# scsi2sd.net
KiCad netlist of a schematic drawn in EAGLE
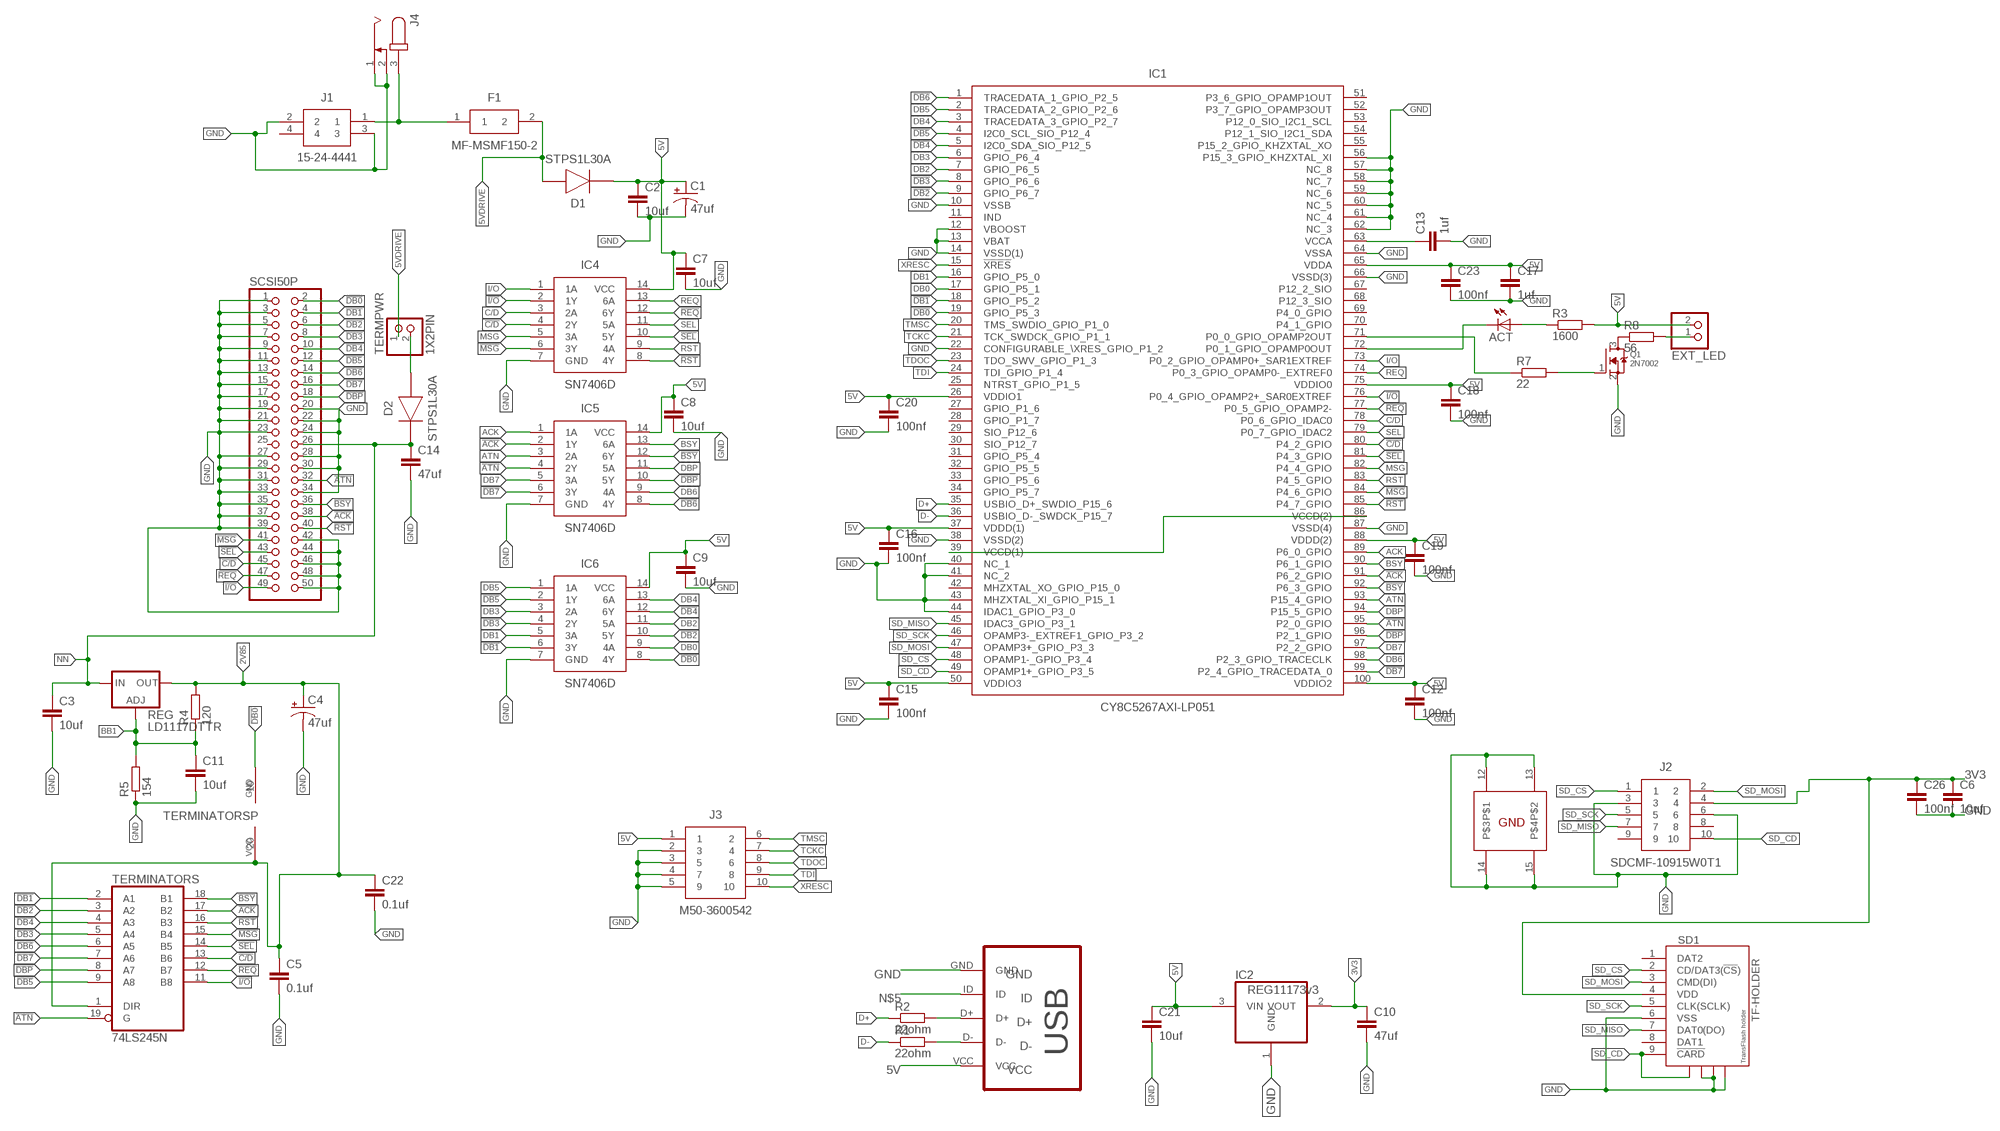
[diagram p0: schematic, sheet 1]

(export (version "E")
  (design (tool "Eeschema 10.0.6"))
  (components
    (comp (ref "ACT")
      (value "LEDCHIPLED_0805")
      (footprint "eagle-import:CHIPLED_0805")
      (libsource (lib "eagle-import") (part "LEDCHIPLED_0805"))
    )
    (comp (ref "C1")
      (value "47uf")
      (footprint "eagle-import:E2,5-5")
      (libsource (lib "eagle-import") (part "CPOL-USE2.5-5"))
    )
    (comp (ref "C2")
      (value "10uf")
      (footprint "eagle-import:C0603")
      (libsource (lib "eagle-import") (part "C-EUC0603"))
    )
    (comp (ref "C3")
      (value "10uf")
      (footprint "eagle-import:C0603")
      (libsource (lib "eagle-import") (part "C-EUC0603"))
    )
    (comp (ref "C4")
      (value "47uf")
      (footprint "eagle-import:E2,5-5")
      (libsource (lib "eagle-import") (part "CPOL-USE2.5-5"))
    )
    (comp (ref "C5")
      (value "0.1uf")
      (footprint "eagle-import:C0603")
      (libsource (lib "eagle-import") (part "C-EUC0603"))
    )
    (comp (ref "C6")
      (value "10uf")
      (footprint "eagle-import:C0603")
      (libsource (lib "eagle-import") (part "C-EUC0603"))
    )
    (comp (ref "C7")
      (value "10uf")
      (footprint "eagle-import:C0603")
      (libsource (lib "eagle-import") (part "C-EUC0603"))
    )
    (comp (ref "C8")
      (value "10uf")
      (footprint "eagle-import:C0603")
      (libsource (lib "eagle-import") (part "C-EUC0603"))
    )
    (comp (ref "C9")
      (value "10uf")
      (footprint "eagle-import:C0603")
      (libsource (lib "eagle-import") (part "C-EUC0603"))
    )
    (comp (ref "C10")
      (value "47uf")
      (footprint "eagle-import:C0603")
      (libsource (lib "eagle-import") (part "C-EUC0603"))
    )
    (comp (ref "C11")
      (value "10uf")
      (footprint "eagle-import:C0603")
      (libsource (lib "eagle-import") (part "C-EUC0603"))
    )
    (comp (ref "C12")
      (value "100nf")
      (footprint "eagle-import:C0603")
      (libsource (lib "eagle-import") (part "C-EUC0603"))
    )
    (comp (ref "C13")
      (value "1uf")
      (footprint "eagle-import:C0603")
      (libsource (lib "eagle-import") (part "C-EUC0603"))
    )
    (comp (ref "C14")
      (value "47uf")
      (footprint "eagle-import:C1206")
      (libsource (lib "eagle-import") (part "C-EUC1206"))
    )
    (comp (ref "C15")
      (value "100nf")
      (footprint "eagle-import:C0603")
      (libsource (lib "eagle-import") (part "C-EUC0603"))
    )
    (comp (ref "C16")
      (value "100nf")
      (footprint "eagle-import:C0603")
      (libsource (lib "eagle-import") (part "C-EUC0603"))
    )
    (comp (ref "C17")
      (value "1uf")
      (footprint "eagle-import:C0603")
      (libsource (lib "eagle-import") (part "C-EUC0603"))
    )
    (comp (ref "C18")
      (value "100nf")
      (footprint "eagle-import:C0603")
      (libsource (lib "eagle-import") (part "C-EUC0603"))
    )
    (comp (ref "C19")
      (value "100nf")
      (footprint "eagle-import:C0603")
      (libsource (lib "eagle-import") (part "C-EUC0603"))
    )
    (comp (ref "C20")
      (value "100nf")
      (footprint "eagle-import:C0603")
      (libsource (lib "eagle-import") (part "C-EUC0603"))
    )
    (comp (ref "C21")
      (value "10uf")
      (footprint "eagle-import:C0603")
      (libsource (lib "eagle-import") (part "C-EUC0603"))
    )
    (comp (ref "C22")
      (value "0.1uf")
      (footprint "eagle-import:C0603")
      (libsource (lib "eagle-import") (part "C-EUC0603"))
    )
    (comp (ref "C23")
      (value "100nf")
      (footprint "eagle-import:C0603")
      (libsource (lib "eagle-import") (part "C-EUC0603"))
    )
    (comp (ref "C26")
      (value "100nf")
      (footprint "eagle-import:C0603")
      (libsource (lib "eagle-import") (part "C-EUC0603"))
    )
    (comp (ref "D1")
      (value "STPS1L30A")
      (footprint "eagle-import:DIOM5226X223N")
      (fields (field (name "RS_PART_NUMBER") "4858061"))
      (libsource (lib "eagle-import") (part "STPS1L30A"))
    )
    (comp (ref "D2")
      (value "STPS1L30A")
      (footprint "eagle-import:DIOM5226X223N")
      (fields (field (name "RS_PART_NUMBER") "4858061"))
      (libsource (lib "eagle-import") (part "STPS1L30A"))
    )
    (comp (ref "EXT_LED")
      (value "1X2PIN")
      (footprint "eagle-import:1X2PIN")
      (libsource (lib "eagle-import") (part "1X2PIN"))
    )
    (comp (ref "F1")
      (value "MF-MSMF150-2")
      (footprint "eagle-import:FUSC4632X85N")
      (fields (field (name "RS_PART_NUMBER") "6478235"))
      (libsource (lib "eagle-import") (part "MF-MSMF150-2"))
    )
    (comp (ref "IC1")
      (value "CY8C5267AXI-LP051")
      (footprint "eagle-import:TQFP50P1600X1600X160-100N")
      (fields (field (name "RS_PART_NUMBER") "8282749"))
      (libsource (lib "eagle-import") (part "CY8C5267AXI-LP051"))
    )
    (comp (ref "IC2")
      (value "REG11173v3")
      (footprint "eagle-import:SOT223")
      (fields (field (name "MPN") "REG1117"))
      (libsource (lib "eagle-import") (part "REG1117"))
    )
    (comp (ref "IC4")
      (value "SN7406D")
      (footprint "eagle-import:SOIC127P600X175-14N")
      (fields (field (name "RS_PART_NUMBER") "6630739"))
      (libsource (lib "eagle-import") (part "SN7406D"))
    )
    (comp (ref "IC5")
      (value "SN7406D")
      (footprint "eagle-import:SOIC127P600X175-14N")
      (fields (field (name "RS_PART_NUMBER") "6630739"))
      (libsource (lib "eagle-import") (part "SN7406D"))
    )
    (comp (ref "IC6")
      (value "SN7406D")
      (footprint "eagle-import:SOIC127P600X175-14N")
      (fields (field (name "RS_PART_NUMBER") "6630739"))
      (libsource (lib "eagle-import") (part "SN7406D"))
    )
    (comp (ref "J1")
      (value "15-24-4441")
      (footprint "eagle-import:15-24-4441")
      (fields (field (name "RS_PART_NUMBER") "6704256"))
      (libsource (lib "eagle-import") (part "15-24-4441"))
    )
    (comp (ref "J2")
      (value "SDCMF-10915W0T1")
      (footprint "eagle-import:SDCMF-10915W0T1")
      (libsource (lib "eagle-import") (part "SDCMF-10915W0T1"))
    )
    (comp (ref "J3")
      (value "M50-3600542")
      (footprint "eagle-import:HARWIN_10PIN_1.27PITCH_SMD")
      (fields (field (name "RS_PART_NUMBER") "1224772"))
      (libsource (lib "eagle-import") (part "M50-3600542"))
    )
    (comp (ref "J4")
      (value "RAPC7120")
      (footprint "eagle-import:RAPC712")
      (libsource (lib "eagle-import") (part "RAPC7120"))
    )
    (comp (ref "Q1")
      (value "2N7002")
      (footprint "eagle-import:SOT23")
      (libsource (lib "eagle-import") (part "MOSFET-NREFLOW"))
    )
    (comp (ref "R1")
      (value "22ohm")
      (footprint "eagle-import:R0603")
      (libsource (lib "eagle-import") (part "R-EU_R0603"))
    )
    (comp (ref "R2")
      (value "22ohm")
      (footprint "eagle-import:R0603")
      (libsource (lib "eagle-import") (part "R-EU_R0603"))
    )
    (comp (ref "R3")
      (value "1600")
      (footprint "eagle-import:R0603")
      (libsource (lib "eagle-import") (part "R-EU_R0603"))
    )
    (comp (ref "R4")
      (value "120")
      (footprint "eagle-import:R0603")
      (libsource (lib "eagle-import") (part "R-EU_R0603"))
    )
    (comp (ref "R5")
      (value "154")
      (footprint "eagle-import:R0603")
      (libsource (lib "eagle-import") (part "R-EU_R0603"))
    )
    (comp (ref "R7")
      (value "22")
      (footprint "eagle-import:R0603")
      (libsource (lib "eagle-import") (part "R-EU_R0603"))
    )
    (comp (ref "R8")
      (value "56")
      (footprint "eagle-import:R0603")
      (libsource (lib "eagle-import") (part "R-EU_R0603"))
    )
    (comp (ref "REG")
      (value "LD1117DTTR")
      (footprint "eagle-import:DPACK")
      (libsource (lib "eagle-import") (part "LD117A?DT12TR"))
    )
    (comp (ref "SCSI50P")
      (value "PINHD-2X25/90")
      (footprint "eagle-import:2X25_90")
      (libsource (lib "eagle-import") (part "PINHD-2X25/90"))
    )
    (comp (ref "SD1")
      (value "TF-HOLDER")
      (footprint "eagle-import:TF-PULL")
      (libsource (lib "eagle-import") (part "TF-HOLDER"))
    )
    (comp (ref "TERMINATORS")
      (value "74LS245N")
      (footprint "eagle-import:DIL20")
      (libsource (lib "eagle-import") (part "74245NLS"))
    )
    (comp (ref "TERMPWR")
      (value "1X2PIN")
      (footprint "eagle-import:1X2PIN")
      (libsource (lib "eagle-import") (part "edu_1X2PIN"))
    )
    (comp (ref "USB")
      (value "MICRO-USB-B")
      (footprint "eagle-import:MICRO_USB_4_LEGS")
      (libsource (lib "eagle-import") (part "MICRO-USB-B"))
    )
  )
  (nets
    (net (code "1") (name "/N$5") (class "Default")
      (node (ref "USB") (pin "ID") (pinfunction "ID_ID") (pintype "bidirectional"))
    )
    (net (code "2") (name "/~{ACK}") (class "Default")
      (node (ref "IC1") (pin "91") (pinfunction "P6_2_GPIO_91") (pintype "input"))
      (node (ref "IC5") (pin "2") (pinfunction "1Y_2") (pintype "input"))
      (node (ref "SCSI50P") (pin "38") (pinfunction "38_38") (pintype "passive"))
      (node (ref "TERMINATORS") (pin "17") (pinfunction "B2_17") (pintype "bidirectional"))
    )
    (net (code "3") (name "/~{ATN}") (class "Default")
      (node (ref "IC1") (pin "95") (pinfunction "P2_0_GPIO_95") (pintype "input"))
      (node (ref "IC5") (pin "4") (pinfunction "2Y_4") (pintype "input"))
      (node (ref "SCSI50P") (pin "32") (pinfunction "32_32") (pintype "passive"))
      (node (ref "TERMINATORS") (pin "19") (pinfunction "G_19") (pintype "input"))
    )
    (net (code "4") (name "/~{BSY}") (class "Default")
      (node (ref "IC1") (pin "92") (pinfunction "P6_3_GPIO_92") (pintype "input"))
      (node (ref "IC5") (pin "12") (pinfunction "6Y_12") (pintype "input"))
      (node (ref "SCSI50P") (pin "36") (pinfunction "36_36") (pintype "passive"))
      (node (ref "TERMINATORS") (pin "18") (pinfunction "B1_18") (pintype "bidirectional"))
    )
    (net (code "5") (name "/~{C{slash}D}") (class "Default")
      (node (ref "IC1") (pin "80") (pinfunction "P4_2_GPIO_80") (pintype "input"))
      (node (ref "IC4") (pin "4") (pinfunction "2Y_4") (pintype "input"))
      (node (ref "SCSI50P") (pin "45") (pinfunction "45_45") (pintype "passive"))
      (node (ref "TERMINATORS") (pin "13") (pinfunction "B6_13") (pintype "bidirectional"))
    )
    (net (code "6") (name "/~{DB0}") (class "Default")
      (node (ref "IC1") (pin "19") (pinfunction "GPIO_P5_3_19") (pintype "input"))
      (node (ref "IC6") (pin "8") (pinfunction "4Y_8") (pintype "input"))
      (node (ref "SCSI50P") (pin "2") (pinfunction "2_2") (pintype "passive"))
      (node (ref "TERMINATORS") (pin "10") (pinfunction "GND_10") (pintype "power_in"))
    )
    (net (code "7") (name "/~{DB1}") (class "Default")
      (node (ref "IC1") (pin "18") (pinfunction "GPIO_P5_2_18") (pintype "input"))
      (node (ref "IC6") (pin "6") (pinfunction "3Y_6") (pintype "input"))
      (node (ref "SCSI50P") (pin "4") (pinfunction "4_4") (pintype "passive"))
      (node (ref "TERMINATORS") (pin "2") (pinfunction "A1_2") (pintype "bidirectional"))
    )
    (net (code "8") (name "/~{DB2}") (class "Default")
      (node (ref "IC1") (pin "9") (pinfunction "GPIO_P6_7_9") (pintype "input"))
      (node (ref "IC6") (pin "10") (pinfunction "5Y_10") (pintype "input"))
      (node (ref "SCSI50P") (pin "6") (pinfunction "6_6") (pintype "passive"))
      (node (ref "TERMINATORS") (pin "3") (pinfunction "A2_3") (pintype "bidirectional"))
    )
    (net (code "9") (name "/~{DB3}") (class "Default")
      (node (ref "IC1") (pin "8") (pinfunction "GPIO_P6_6_8") (pintype "input"))
      (node (ref "IC6") (pin "4") (pinfunction "2Y_4") (pintype "input"))
      (node (ref "SCSI50P") (pin "8") (pinfunction "8_8") (pintype "passive"))
      (node (ref "TERMINATORS") (pin "5") (pinfunction "A4_5") (pintype "bidirectional"))
    )
    (net (code "10") (name "/~{DB4}") (class "Default")
      (node (ref "IC1") (pin "5") (pinfunction "I2C0_SDA_SIO_P12_5_5") (pintype "input"))
      (node (ref "IC6") (pin "12") (pinfunction "6Y_12") (pintype "input"))
      (node (ref "SCSI50P") (pin "10") (pinfunction "10_10") (pintype "passive"))
      (node (ref "TERMINATORS") (pin "4") (pinfunction "A3_4") (pintype "bidirectional"))
    )
    (net (code "11") (name "/~{DB5}") (class "Default")
      (node (ref "IC1") (pin "4") (pinfunction "I2C0_SCL_SIO_P12_4_4") (pintype "input"))
      (node (ref "IC6") (pin "2") (pinfunction "1Y_2") (pintype "input"))
      (node (ref "SCSI50P") (pin "12") (pinfunction "12_12") (pintype "passive"))
      (node (ref "TERMINATORS") (pin "9") (pinfunction "A8_9") (pintype "bidirectional"))
    )
    (net (code "12") (name "/~{DB6}") (class "Default")
      (node (ref "IC1") (pin "1") (pinfunction "TRACEDATA_1_GPIO_P2_5_1") (pintype "input"))
      (node (ref "IC5") (pin "8") (pinfunction "4Y_8") (pintype "input"))
      (node (ref "SCSI50P") (pin "14") (pinfunction "14_14") (pintype "passive"))
      (node (ref "TERMINATORS") (pin "6") (pinfunction "A5_6") (pintype "bidirectional"))
    )
    (net (code "13") (name "/~{DB7}") (class "Default")
      (node (ref "IC1") (pin "99") (pinfunction "P2_4_GPIO_TRACEDATA_0_99") (pintype "input"))
      (node (ref "IC5") (pin "6") (pinfunction "3Y_6") (pintype "input"))
      (node (ref "SCSI50P") (pin "16") (pinfunction "16_16") (pintype "passive"))
      (node (ref "TERMINATORS") (pin "7") (pinfunction "A6_7") (pintype "bidirectional"))
    )
    (net (code "14") (name "/~{DBP}") (class "Default")
      (node (ref "IC1") (pin "96") (pinfunction "P2_1_GPIO_96") (pintype "input"))
      (node (ref "IC5") (pin "10") (pinfunction "5Y_10") (pintype "input"))
      (node (ref "SCSI50P") (pin "18") (pinfunction "18_18") (pintype "passive"))
      (node (ref "TERMINATORS") (pin "8") (pinfunction "A7_8") (pintype "bidirectional"))
    )
    (net (code "15") (name "/~{I{slash}O}") (class "Default")
      (node (ref "IC1") (pin "76") (pinfunction "P0_4_GPIO_OPAMP2+_SAR0EXTREF_76") (pintype "input"))
      (node (ref "IC4") (pin "2") (pinfunction "1Y_2") (pintype "input"))
      (node (ref "SCSI50P") (pin "49") (pinfunction "49_49") (pintype "passive"))
      (node (ref "TERMINATORS") (pin "11") (pinfunction "B8_11") (pintype "bidirectional"))
    )
    (net (code "16") (name "/~{MSG}") (class "Default")
      (node (ref "IC1") (pin "84") (pinfunction "P4_6_GPIO_84") (pintype "input"))
      (node (ref "IC4") (pin "6") (pinfunction "3Y_6") (pintype "input"))
      (node (ref "SCSI50P") (pin "41") (pinfunction "41_41") (pintype "passive"))
      (node (ref "TERMINATORS") (pin "15") (pinfunction "B4_15") (pintype "bidirectional"))
    )
    (net (code "17") (name "/~{REQ}") (class "Default")
      (node (ref "IC1") (pin "77") (pinfunction "P0_5_GPIO_OPAMP2-_77") (pintype "input"))
      (node (ref "IC4") (pin "12") (pinfunction "6Y_12") (pintype "input"))
      (node (ref "SCSI50P") (pin "47") (pinfunction "47_47") (pintype "passive"))
      (node (ref "TERMINATORS") (pin "12") (pinfunction "B7_12") (pintype "bidirectional"))
    )
    (net (code "18") (name "/~{RST}") (class "Default")
      (node (ref "IC1") (pin "85") (pinfunction "P4_7_GPIO_85") (pintype "input"))
      (node (ref "IC4") (pin "8") (pinfunction "4Y_8") (pintype "input"))
      (node (ref "SCSI50P") (pin "40") (pinfunction "40_40") (pintype "passive"))
      (node (ref "TERMINATORS") (pin "16") (pinfunction "B3_16") (pintype "bidirectional"))
    )
    (net (code "19") (name "/~{SEL}") (class "Default")
      (node (ref "IC1") (pin "81") (pinfunction "P4_3_GPIO_81") (pintype "input"))
      (node (ref "IC4") (pin "10") (pinfunction "5Y_10") (pintype "input"))
      (node (ref "SCSI50P") (pin "43") (pinfunction "43_43") (pintype "passive"))
      (node (ref "TERMINATORS") (pin "14") (pinfunction "B5_14") (pintype "bidirectional"))
    )
    (net (code "20") (name "2V85") (class "Default")
      (node (ref "C22") (pin "1") (pinfunction "1_1") (pintype "passive"))
      (node (ref "C4") (pin "+") (pinfunction "+_+") (pintype "passive"))
      (node (ref "C5") (pin "1") (pinfunction "1_1") (pintype "passive"))
      (node (ref "R4") (pin "2") (pinfunction "2_2") (pintype "passive"))
      (node (ref "REG") (pin "4") (pinfunction "OUT_4") (pintype "passive"))
      (node (ref "TERMINATORS") (pin "1") (pinfunction "DIR_1") (pintype "input"))
      (node (ref "TERMINATORS") (pin "20") (pinfunction "VCC_20") (pintype "power_in"))
    )
    (net (code "21") (name "3V3") (class "Default")
      (node (ref "C10") (pin "1") (pinfunction "1_1") (pintype "passive"))
      (node (ref "C26") (pin "1") (pinfunction "1_1") (pintype "passive"))
      (node (ref "C6") (pin "1") (pinfunction "1_1") (pintype "passive"))
      (node (ref "IC2") (pin "2") (pinfunction "VOUT_2") (pintype "output"))
      (node (ref "J2") (pin "4") (pinfunction "4_4") (pintype "input"))
      (node (ref "SD1") (pin "4") (pinfunction "VDD_4") (pintype "power_in"))
    )
    (net (code "22") (name "5V") (class "Default")
      (node (ref "C1") (pin "+") (pinfunction "+_+") (pintype "passive"))
      (node (ref "C12") (pin "1") (pinfunction "1_1") (pintype "passive"))
      (node (ref "C15") (pin "1") (pinfunction "1_1") (pintype "passive"))
      (node (ref "C16") (pin "1") (pinfunction "1_1") (pintype "passive"))
      (node (ref "C17") (pin "1") (pinfunction "1_1") (pintype "passive"))
      (node (ref "C18") (pin "1") (pinfunction "1_1") (pintype "passive"))
      (node (ref "C19") (pin "1") (pinfunction "1_1") (pintype "passive"))
      (node (ref "C2") (pin "1") (pinfunction "1_1") (pintype "passive"))
      (node (ref "C20") (pin "1") (pinfunction "1_1") (pintype "passive"))
      (node (ref "C21") (pin "1") (pinfunction "1_1") (pintype "passive"))
      (node (ref "C23") (pin "1") (pinfunction "1_1") (pintype "passive"))
      (node (ref "C7") (pin "1") (pinfunction "1_1") (pintype "passive"))
      (node (ref "C8") (pin "1") (pinfunction "1_1") (pintype "passive"))
      (node (ref "C9") (pin "1") (pinfunction "1_1") (pintype "passive"))
      (node (ref "D1") (pin "1") (pinfunction "K_1") (pintype "bidirectional"))
      (node (ref "EXT_LED") (pin "2") (pinfunction "2_2") (pintype "passive"))
      (node (ref "IC1") (pin "100") (pinfunction "VDDIO2_100") (pintype "input"))
      (node (ref "IC1") (pin "26") (pinfunction "VDDIO1_26") (pintype "input"))
      (node (ref "IC1") (pin "37") (pinfunction "VDDD(1)_37") (pintype "input"))
      (node (ref "IC1") (pin "50") (pinfunction "VDDIO3_50") (pintype "input"))
      (node (ref "IC1") (pin "65") (pinfunction "VDDA_65") (pintype "input"))
      (node (ref "IC1") (pin "75") (pinfunction "VDDIO0_75") (pintype "input"))
      (node (ref "IC1") (pin "88") (pinfunction "VDDD(2)_88") (pintype "input"))
      (node (ref "IC2") (pin "3") (pinfunction "VIN_3") (pintype "input"))
      (node (ref "IC4") (pin "14") (pinfunction "VCC_14") (pintype "input"))
      (node (ref "IC5") (pin "14") (pinfunction "VCC_14") (pintype "input"))
      (node (ref "IC6") (pin "14") (pinfunction "VCC_14") (pintype "input"))
      (node (ref "J3") (pin "1") (pinfunction "1_1") (pintype "input"))
      (node (ref "R3") (pin "2") (pinfunction "2_2") (pintype "passive"))
      (node (ref "USB") (pin "VCC") (pinfunction "VCC_VCC") (pintype "bidirectional"))
    )
    (net (code "23") (name "5VDRIVE") (class "Default")
      (node (ref "D1") (pin "2") (pinfunction "A_2") (pintype "bidirectional"))
      (node (ref "F1") (pin "2") (pinfunction "2_2") (pintype "input"))
      (node (ref "TERMPWR") (pin "1") (pinfunction "1_1") (pintype "passive"))
    )
    (net (code "24") (name "ACK") (class "Default")
      (node (ref "IC1") (pin "89") (pinfunction "P6_0_GPIO_89") (pintype "input"))
      (node (ref "IC5") (pin "1") (pinfunction "1A_1") (pintype "input"))
    )
    (net (code "25") (name "ATN") (class "Default")
      (node (ref "IC1") (pin "93") (pinfunction "P15_4_GPIO_93") (pintype "input"))
      (node (ref "IC5") (pin "3") (pinfunction "2A_3") (pintype "input"))
    )
    (net (code "26") (name "BB1") (class "Default")
      (node (ref "C11") (pin "1") (pinfunction "1_1") (pintype "passive"))
      (node (ref "R4") (pin "1") (pinfunction "1_1") (pintype "passive"))
      (node (ref "R5") (pin "2") (pinfunction "2_2") (pintype "passive"))
      (node (ref "REG") (pin "1") (pinfunction "ADJ_1") (pintype "input"))
    )
    (net (code "27") (name "BSY") (class "Default")
      (node (ref "IC1") (pin "90") (pinfunction "P6_1_GPIO_90") (pintype "input"))
      (node (ref "IC5") (pin "13") (pinfunction "6A_13") (pintype "input"))
    )
    (net (code "28") (name "C{slash}D") (class "Default")
      (node (ref "IC1") (pin "78") (pinfunction "P0_6_GPIO_IDAC0_78") (pintype "input"))
      (node (ref "IC4") (pin "3") (pinfunction "2A_3") (pintype "input"))
    )
    (net (code "29") (name "D+") (class "Default")
      (node (ref "IC1") (pin "35") (pinfunction "USBIO_D+_SWDIO_P15_6_35") (pintype "input"))
      (node (ref "R2") (pin "1") (pinfunction "1_1") (pintype "passive"))
    )
    (net (code "30") (name "D-") (class "Default")
      (node (ref "IC1") (pin "36") (pinfunction "USBIO_D-_SWDCK_P15_7_36") (pintype "input"))
      (node (ref "R1") (pin "1") (pinfunction "1_1") (pintype "passive"))
    )
    (net (code "31") (name "DB0") (class "Default")
      (node (ref "IC1") (pin "17") (pinfunction "GPIO_P5_1_17") (pintype "input"))
      (node (ref "IC6") (pin "9") (pinfunction "4A_9") (pintype "input"))
    )
    (net (code "32") (name "DB1") (class "Default")
      (node (ref "IC1") (pin "16") (pinfunction "GPIO_P5_0_16") (pintype "input"))
      (node (ref "IC6") (pin "5") (pinfunction "3A_5") (pintype "input"))
    )
    (net (code "33") (name "DB2") (class "Default")
      (node (ref "IC1") (pin "7") (pinfunction "GPIO_P6_5_7") (pintype "input"))
      (node (ref "IC6") (pin "11") (pinfunction "5A_11") (pintype "input"))
    )
    (net (code "34") (name "DB3") (class "Default")
      (node (ref "IC1") (pin "6") (pinfunction "GPIO_P6_4_6") (pintype "input"))
      (node (ref "IC6") (pin "3") (pinfunction "2A_3") (pintype "input"))
    )
    (net (code "35") (name "DB4") (class "Default")
      (node (ref "IC1") (pin "3") (pinfunction "TRACEDATA_3_GPIO_P2_7_3") (pintype "input"))
      (node (ref "IC6") (pin "13") (pinfunction "6A_13") (pintype "input"))
    )
    (net (code "36") (name "DB5") (class "Default")
      (node (ref "IC1") (pin "2") (pinfunction "TRACEDATA_2_GPIO_P2_6_2") (pintype "input"))
      (node (ref "IC6") (pin "1") (pinfunction "1A_1") (pintype "input"))
    )
    (net (code "37") (name "DB6") (class "Default")
      (node (ref "IC1") (pin "98") (pinfunction "P2_3_GPIO_TRACECLK_98") (pintype "input"))
      (node (ref "IC5") (pin "9") (pinfunction "4A_9") (pintype "input"))
    )
    (net (code "38") (name "DB7") (class "Default")
      (node (ref "IC1") (pin "97") (pinfunction "P2_2_GPIO_97") (pintype "input"))
      (node (ref "IC5") (pin "5") (pinfunction "3A_5") (pintype "input"))
    )
    (net (code "39") (name "DBP") (class "Default")
      (node (ref "IC1") (pin "94") (pinfunction "P15_5_GPIO_94") (pintype "input"))
      (node (ref "IC5") (pin "11") (pinfunction "5A_11") (pintype "input"))
    )
    (net (code "40") (name "GND") (class "Default")
      (node (ref "C1") (pin "-") (pinfunction "-_-") (pintype "passive"))
      (node (ref "C10") (pin "2") (pinfunction "2_2") (pintype "passive"))
      (node (ref "C11") (pin "2") (pinfunction "2_2") (pintype "passive"))
      (node (ref "C12") (pin "2") (pinfunction "2_2") (pintype "passive"))
      (node (ref "C13") (pin "2") (pinfunction "2_2") (pintype "passive"))
      (node (ref "C14") (pin "2") (pinfunction "2_2") (pintype "passive"))
      (node (ref "C15") (pin "2") (pinfunction "2_2") (pintype "passive"))
      (node (ref "C16") (pin "2") (pinfunction "2_2") (pintype "passive"))
      (node (ref "C17") (pin "2") (pinfunction "2_2") (pintype "passive"))
      (node (ref "C18") (pin "2") (pinfunction "2_2") (pintype "passive"))
      (node (ref "C19") (pin "2") (pinfunction "2_2") (pintype "passive"))
      (node (ref "C2") (pin "2") (pinfunction "2_2") (pintype "passive"))
      (node (ref "C20") (pin "2") (pinfunction "2_2") (pintype "passive"))
      (node (ref "C21") (pin "2") (pinfunction "2_2") (pintype "passive"))
      (node (ref "C22") (pin "2") (pinfunction "2_2") (pintype "passive"))
      (node (ref "C23") (pin "2") (pinfunction "2_2") (pintype "passive"))
      (node (ref "C26") (pin "2") (pinfunction "2_2") (pintype "passive"))
      (node (ref "C3") (pin "2") (pinfunction "2_2") (pintype "passive"))
      (node (ref "C4") (pin "-") (pinfunction "-_-") (pintype "passive"))
      (node (ref "C5") (pin "2") (pinfunction "2_2") (pintype "passive"))
      (node (ref "C6") (pin "2") (pinfunction "2_2") (pintype "passive"))
      (node (ref "C7") (pin "2") (pinfunction "2_2") (pintype "passive"))
      (node (ref "C8") (pin "2") (pinfunction "2_2") (pintype "passive"))
      (node (ref "C9") (pin "2") (pinfunction "2_2") (pintype "passive"))
      (node (ref "IC1") (pin "10") (pinfunction "VSSB_10") (pintype "input"))
      (node (ref "IC1") (pin "12") (pinfunction "VBOOST_12") (pintype "input"))
      (node (ref "IC1") (pin "13") (pinfunction "VBAT_13") (pintype "input"))
      (node (ref "IC1") (pin "14") (pinfunction "VSSD(1)_14") (pintype "input"))
      (node (ref "IC1") (pin "22") (pinfunction "CONFIGURABLE_\\XRES_GPIO_P1_2_22") (pintype "input"))
      (node (ref "IC1") (pin "38") (pinfunction "VSSD(2)_38") (pintype "input"))
      (node (ref "IC1") (pin "40") (pinfunction "NC_1_40") (pintype "input"))
      (node (ref "IC1") (pin "41") (pinfunction "NC_2_41") (pintype "input"))
      (node (ref "IC1") (pin "43") (pinfunction "MHZXTAL_XI_GPIO_P15_1_43") (pintype "input"))
      (node (ref "IC1") (pin "44") (pinfunction "IDAC1_GPIO_P3_0_44") (pintype "input"))
      (node (ref "IC1") (pin "56") (pinfunction "P15_3_GPIO_KHZXTAL_XI_56") (pintype "input"))
      (node (ref "IC1") (pin "57") (pinfunction "NC_8_57") (pintype "input"))
      (node (ref "IC1") (pin "58") (pinfunction "NC_7_58") (pintype "input"))
      (node (ref "IC1") (pin "59") (pinfunction "NC_6_59") (pintype "input"))
      (node (ref "IC1") (pin "60") (pinfunction "NC_5_60") (pintype "input"))
      (node (ref "IC1") (pin "61") (pinfunction "NC_4_61") (pintype "input"))
      (node (ref "IC1") (pin "62") (pinfunction "NC_3_62") (pintype "input"))
      (node (ref "IC1") (pin "64") (pinfunction "VSSA_64") (pintype "input"))
      (node (ref "IC1") (pin "66") (pinfunction "VSSD(3)_66") (pintype "input"))
      (node (ref "IC1") (pin "87") (pinfunction "VSSD(4)_87") (pintype "input"))
      (node (ref "IC2") (pin "1") (pinfunction "GND_1") (pintype "power_in"))
      (node (ref "IC4") (pin "7") (pinfunction "GND_7") (pintype "input"))
      (node (ref "IC5") (pin "7") (pinfunction "GND_7") (pintype "input"))
      (node (ref "IC6") (pin "7") (pinfunction "GND_7") (pintype "input"))
      (node (ref "J1") (pin "2") (pinfunction "2_2") (pintype "input"))
      (node (ref "J1") (pin "3") (pinfunction "3_3") (pintype "input"))
      (node (ref "J2") (pin "12") (pinfunction "P$1_12") (pintype "bidirectional"))
      (node (ref "J2") (pin "13") (pinfunction "P$2_13") (pintype "bidirectional"))
      (node (ref "J2") (pin "14") (pinfunction "P$3_14") (pintype "bidirectional"))
      (node (ref "J2") (pin "15") (pinfunction "P$4_15") (pintype "bidirectional"))
      (node (ref "J2") (pin "3") (pinfunction "3_3") (pintype "input"))
      (node (ref "J2") (pin "6") (pinfunction "6_6") (pintype "input"))
      (node (ref "J3") (pin "2") (pinfunction "3_2") (pintype "input"))
      (node (ref "J3") (pin "3") (pinfunction "5_3") (pintype "input"))
      (node (ref "J3") (pin "4") (pinfunction "7_4") (pintype "input"))
      (node (ref "J3") (pin "5") (pinfunction "9_5") (pintype "input"))
      (node (ref "J4") (pin "1") (pinfunction "1_1") (pintype "passive"))
      (node (ref "J4") (pin "2") (pinfunction "2_2") (pintype "passive"))
      (node (ref "Q1") (pin "2") (pinfunction "S_2") (pintype "bidirectional"))
      (node (ref "R5") (pin "1") (pinfunction "1_1") (pintype "passive"))
      (node (ref "SCSI50P") (pin "1") (pinfunction "1_1") (pintype "passive"))
      (node (ref "SCSI50P") (pin "11") (pinfunction "11_11") (pintype "passive"))
      (node (ref "SCSI50P") (pin "13") (pinfunction "13_13") (pintype "passive"))
      (node (ref "SCSI50P") (pin "15") (pinfunction "15_15") (pintype "passive"))
      (node (ref "SCSI50P") (pin "17") (pinfunction "17_17") (pintype "passive"))
      (node (ref "SCSI50P") (pin "19") (pinfunction "19_19") (pintype "passive"))
      (node (ref "SCSI50P") (pin "20") (pinfunction "20_20") (pintype "passive"))
      (node (ref "SCSI50P") (pin "21") (pinfunction "21_21") (pintype "passive"))
      (node (ref "SCSI50P") (pin "22") (pinfunction "22_22") (pintype "passive"))
      (node (ref "SCSI50P") (pin "23") (pinfunction "23_23") (pintype "passive"))
      (node (ref "SCSI50P") (pin "24") (pinfunction "24_24") (pintype "passive"))
      (node (ref "SCSI50P") (pin "27") (pinfunction "27_27") (pintype "passive"))
      (node (ref "SCSI50P") (pin "28") (pinfunction "28_28") (pintype "passive"))
      (node (ref "SCSI50P") (pin "29") (pinfunction "29_29") (pintype "passive"))
      (node (ref "SCSI50P") (pin "3") (pinfunction "3_3") (pintype "passive"))
      (node (ref "SCSI50P") (pin "30") (pinfunction "30_30") (pintype "passive"))
      (node (ref "SCSI50P") (pin "31") (pinfunction "31_31") (pintype "passive"))
      (node (ref "SCSI50P") (pin "33") (pinfunction "33_33") (pintype "passive"))
      (node (ref "SCSI50P") (pin "34") (pinfunction "34_34") (pintype "passive"))
      (node (ref "SCSI50P") (pin "35") (pinfunction "35_35") (pintype "passive"))
      (node (ref "SCSI50P") (pin "37") (pinfunction "37_37") (pintype "passive"))
      (node (ref "SCSI50P") (pin "39") (pinfunction "39_39") (pintype "passive"))
      (node (ref "SCSI50P") (pin "42") (pinfunction "42_42") (pintype "passive"))
      (node (ref "SCSI50P") (pin "44") (pinfunction "44_44") (pintype "passive"))
      (node (ref "SCSI50P") (pin "46") (pinfunction "46_46") (pintype "passive"))
      (node (ref "SCSI50P") (pin "48") (pinfunction "48_48") (pintype "passive"))
      (node (ref "SCSI50P") (pin "5") (pinfunction "5_5") (pintype "passive"))
      (node (ref "SCSI50P") (pin "50") (pinfunction "50_50") (pintype "passive"))
      (node (ref "SCSI50P") (pin "7") (pinfunction "7_7") (pintype "passive"))
      (node (ref "SCSI50P") (pin "9") (pinfunction "9_9") (pintype "passive"))
      (node (ref "SD1") (pin "6") (pinfunction "VSS_6") (pintype "power_in"))
      (node (ref "SD1") (pin "S2") (pinfunction "S2_S2") (pintype "passive"))
      (node (ref "SD1") (pin "S3") (pinfunction "S3_S3") (pintype "passive"))
      (node (ref "SD1") (pin "S4") (pinfunction "S4_S4") (pintype "passive"))
      (node (ref "USB") (pin "GND") (pinfunction "GND_GND") (pintype "bidirectional"))
    )
    (net (code "41") (name "I{slash}O") (class "Default")
      (node (ref "IC1") (pin "73") (pinfunction "P0_2_GPIO_OPAMP0+_SAR1EXTREF_73") (pintype "input"))
      (node (ref "IC4") (pin "1") (pinfunction "1A_1") (pintype "input"))
    )
    (net (code "42") (name "MSG") (class "Default")
      (node (ref "IC1") (pin "82") (pinfunction "P4_4_GPIO_82") (pintype "input"))
      (node (ref "IC4") (pin "5") (pinfunction "3A_5") (pintype "input"))
    )
    (net (code "43") (name "NN") (class "Default")
      (node (ref "C14") (pin "1") (pinfunction "1_1") (pintype "passive"))
      (node (ref "C3") (pin "1") (pinfunction "1_1") (pintype "passive"))
      (node (ref "D2") (pin "1") (pinfunction "K_1") (pintype "bidirectional"))
      (node (ref "REG") (pin "3") (pinfunction "IN_3") (pintype "input"))
      (node (ref "SCSI50P") (pin "26") (pinfunction "26_26") (pintype "passive"))
    )
    (net (code "44") (name "Net-(ACT-PadA)") (class "Default")
      (node (ref "ACT") (pin "A") (pinfunction "A_A") (pintype "passive"))
      (node (ref "R3") (pin "1") (pinfunction "1_1") (pintype "passive"))
    )
    (net (code "45") (name "Net-(D2-A)") (class "Default")
      (node (ref "D2") (pin "2") (pinfunction "A_2") (pintype "bidirectional"))
      (node (ref "TERMPWR") (pin "2") (pinfunction "2_2") (pintype "passive"))
    )
    (net (code "46") (name "Net-(EXT_LED-Pad1)") (class "Default")
      (node (ref "EXT_LED") (pin "1") (pinfunction "1_1") (pintype "passive"))
      (node (ref "R8") (pin "2") (pinfunction "2_2") (pintype "passive"))
    )
    (net (code "47") (name "Net-(F1-Pad1)") (class "Default")
      (node (ref "F1") (pin "1") (pinfunction "1_1") (pintype "input"))
      (node (ref "J1") (pin "1") (pinfunction "1_1") (pintype "input"))
      (node (ref "J4") (pin "3") (pinfunction "3_3") (pintype "passive"))
    )
    (net (code "48") (name "Net-(IC1-P0_0_GPIO_OPAMP2OUT)") (class "Default")
      (node (ref "IC1") (pin "71") (pinfunction "P0_0_GPIO_OPAMP2OUT_71") (pintype "input"))
      (node (ref "R7") (pin "1") (pinfunction "1_1") (pintype "passive"))
    )
    (net (code "49") (name "Net-(IC1-P0_1_GPIO_OPAMP0OUT)") (class "Default")
      (node (ref "ACT") (pin "C") (pinfunction "C_C") (pintype "passive"))
      (node (ref "IC1") (pin "72") (pinfunction "P0_1_GPIO_OPAMP0OUT_72") (pintype "input"))
    )
    (net (code "50") (name "Net-(IC1-VCCA)") (class "Default")
      (node (ref "C13") (pin "1") (pinfunction "1_1") (pintype "passive"))
      (node (ref "IC1") (pin "63") (pinfunction "VCCA_63") (pintype "input"))
    )
    (net (code "51") (name "Net-(IC1-VCCD(1))") (class "Default")
      (node (ref "IC1") (pin "39") (pinfunction "VCCD(1)_39") (pintype "input"))
      (node (ref "IC1") (pin "86") (pinfunction "VCCD(2)_86") (pintype "input"))
    )
    (net (code "52") (name "Net-(Q1-D)") (class "Default")
      (node (ref "Q1") (pin "3") (pinfunction "D_3") (pintype "bidirectional"))
      (node (ref "R8") (pin "1") (pinfunction "1_1") (pintype "passive"))
    )
    (net (code "53") (name "Net-(Q1-G)") (class "Default")
      (node (ref "Q1") (pin "1") (pinfunction "G_1") (pintype "bidirectional"))
      (node (ref "R7") (pin "2") (pinfunction "2_2") (pintype "passive"))
    )
    (net (code "54") (name "Net-(R1-Pad2)") (class "Default")
      (node (ref "R1") (pin "2") (pinfunction "2_2") (pintype "passive"))
      (node (ref "USB") (pin "D-") (pinfunction "D-_D-") (pintype "bidirectional"))
    )
    (net (code "55") (name "Net-(R2-Pad2)") (class "Default")
      (node (ref "R2") (pin "2") (pinfunction "2_2") (pintype "passive"))
      (node (ref "USB") (pin "D+") (pinfunction "D+_D+") (pintype "bidirectional"))
    )
    (net (code "56") (name "REQ") (class "Default")
      (node (ref "IC1") (pin "74") (pinfunction "P0_3_GPIO_OPAMP0-_EXTREF0_74") (pintype "input"))
      (node (ref "IC4") (pin "13") (pinfunction "6A_13") (pintype "input"))
    )
    (net (code "57") (name "RST") (class "Default")
      (node (ref "IC1") (pin "83") (pinfunction "P4_5_GPIO_83") (pintype "input"))
      (node (ref "IC4") (pin "9") (pinfunction "4A_9") (pintype "input"))
    )
    (net (code "58") (name "SD_CD") (class "Default")
      (node (ref "IC1") (pin "49") (pinfunction "OPAMP1+_GPIO_P3_5_49") (pintype "input"))
      (node (ref "J2") (pin "10") (pinfunction "10_10") (pintype "bidirectional"))
      (node (ref "SD1") (pin "9") (pinfunction "~{CARD}_9") (pintype "passive"))
      (node (ref "SD1") (pin "S1") (pinfunction "S1_S1") (pintype "passive"))
    )
    (net (code "59") (name "SD_CS") (class "Default")
      (node (ref "IC1") (pin "48") (pinfunction "OPAMP1-_GPIO_P3_4_48") (pintype "input"))
      (node (ref "J2") (pin "1") (pinfunction "1_1") (pintype "input"))
      (node (ref "SD1") (pin "2") (pinfunction "CD/DAT3(~{CS})_2") (pintype "bidirectional"))
    )
    (net (code "60") (name "SD_MISO") (class "Default")
      (node (ref "IC1") (pin "45") (pinfunction "IDAC3_GPIO_P3_1_45") (pintype "input"))
      (node (ref "J2") (pin "7") (pinfunction "7_7") (pintype "input"))
      (node (ref "SD1") (pin "7") (pinfunction "DAT0(DO)_7") (pintype "bidirectional"))
    )
    (net (code "61") (name "SD_MOSI") (class "Default")
      (node (ref "IC1") (pin "47") (pinfunction "OPAMP3+_GPIO_P3_3_47") (pintype "input"))
      (node (ref "J2") (pin "2") (pinfunction "2_2") (pintype "input"))
      (node (ref "SD1") (pin "3") (pinfunction "CMD(DI)_3") (pintype "bidirectional"))
    )
    (net (code "62") (name "SD_SCK") (class "Default")
      (node (ref "IC1") (pin "46") (pinfunction "OPAMP3-_EXTREF1_GPIO_P3_2_46") (pintype "input"))
      (node (ref "J2") (pin "5") (pinfunction "5_5") (pintype "input"))
      (node (ref "SD1") (pin "5") (pinfunction "CLK(SCLK)_5") (pintype "input"))
    )
    (net (code "63") (name "SEL") (class "Default")
      (node (ref "IC1") (pin "79") (pinfunction "P0_7_GPIO_IDAC2_79") (pintype "input"))
      (node (ref "IC4") (pin "11") (pinfunction "5A_11") (pintype "input"))
    )
    (net (code "64") (name "TCKC") (class "Default")
      (node (ref "IC1") (pin "21") (pinfunction "TCK_SWDCK_GPIO_P1_1_21") (pintype "input"))
      (node (ref "J3") (pin "7") (pinfunction "4_7") (pintype "input"))
    )
    (net (code "65") (name "TDI") (class "Default")
      (node (ref "IC1") (pin "24") (pinfunction "TDI_GPIO_P1_4_24") (pintype "input"))
      (node (ref "J3") (pin "9") (pinfunction "8_9") (pintype "input"))
    )
    (net (code "66") (name "TDOC") (class "Default")
      (node (ref "IC1") (pin "23") (pinfunction "TDO_SWV_GPIO_P1_3_23") (pintype "input"))
      (node (ref "J3") (pin "8") (pinfunction "6_8") (pintype "input"))
    )
    (net (code "67") (name "TMSC") (class "Default")
      (node (ref "IC1") (pin "20") (pinfunction "TMS_SWDIO_GPIO_P1_0_20") (pintype "input"))
      (node (ref "J3") (pin "6") (pinfunction "2_6") (pintype "input"))
    )
    (net (code "68") (name "XRESC") (class "Default")
      (node (ref "IC1") (pin "15") (pinfunction "~{XRES}_15") (pintype "input"))
      (node (ref "J3") (pin "10") (pinfunction "10_10") (pintype "input"))
    )
    (net (code "69") (name "unconnected-(IC1-GPIO_P1_6-Pad27)") (class "Default")
      (node (ref "IC1") (pin "27") (pinfunction "GPIO_P1_6_27") (pintype "input"))
    )
    (net (code "70") (name "unconnected-(IC1-GPIO_P1_7-Pad28)") (class "Default")
      (node (ref "IC1") (pin "28") (pinfunction "GPIO_P1_7_28") (pintype "input"))
    )
    (net (code "71") (name "unconnected-(IC1-GPIO_P5_4-Pad31)") (class "Default")
      (node (ref "IC1") (pin "31") (pinfunction "GPIO_P5_4_31") (pintype "input"))
    )
    (net (code "72") (name "unconnected-(IC1-GPIO_P5_5-Pad32)") (class "Default")
      (node (ref "IC1") (pin "32") (pinfunction "GPIO_P5_5_32") (pintype "input"))
    )
    (net (code "73") (name "unconnected-(IC1-GPIO_P5_6-Pad33)") (class "Default")
      (node (ref "IC1") (pin "33") (pinfunction "GPIO_P5_6_33") (pintype "input"))
    )
    (net (code "74") (name "unconnected-(IC1-GPIO_P5_7-Pad34)") (class "Default")
      (node (ref "IC1") (pin "34") (pinfunction "GPIO_P5_7_34") (pintype "input"))
    )
    (net (code "75") (name "unconnected-(IC1-IND-Pad11)") (class "Default")
      (node (ref "IC1") (pin "11") (pinfunction "IND_11") (pintype "input"))
    )
    (net (code "76") (name "unconnected-(IC1-MHZXTAL_XO_GPIO_P15_0-Pad42)") (class "Default")
      (node (ref "IC1") (pin "42") (pinfunction "MHZXTAL_XO_GPIO_P15_0_42") (pintype "input"))
    )
    (net (code "77") (name "unconnected-(IC1-NTRST_GPIO_P1_5-Pad25)") (class "Default")
      (node (ref "IC1") (pin "25") (pinfunction "NTRST_GPIO_P1_5_25") (pintype "input"))
    )
    (net (code "78") (name "unconnected-(IC1-P3_6_GPIO_OPAMP1OUT-Pad51)") (class "Default")
      (node (ref "IC1") (pin "51") (pinfunction "P3_6_GPIO_OPAMP1OUT_51") (pintype "input"))
    )
    (net (code "79") (name "unconnected-(IC1-P3_7_GPIO_OPAMP3OUT-Pad52)") (class "Default")
      (node (ref "IC1") (pin "52") (pinfunction "P3_7_GPIO_OPAMP3OUT_52") (pintype "input"))
    )
    (net (code "80") (name "unconnected-(IC1-P4_0_GPIO-Pad69)") (class "Default")
      (node (ref "IC1") (pin "69") (pinfunction "P4_0_GPIO_69") (pintype "input"))
    )
    (net (code "81") (name "unconnected-(IC1-P4_1_GPIO-Pad70)") (class "Default")
      (node (ref "IC1") (pin "70") (pinfunction "P4_1_GPIO_70") (pintype "input"))
    )
    (net (code "82") (name "unconnected-(IC1-P12_0_SIO_I2C1_SCL-Pad53)") (class "Default")
      (node (ref "IC1") (pin "53") (pinfunction "P12_0_SIO_I2C1_SCL_53") (pintype "input"))
    )
    (net (code "83") (name "unconnected-(IC1-P12_1_SIO_I2C1_SDA-Pad54)") (class "Default")
      (node (ref "IC1") (pin "54") (pinfunction "P12_1_SIO_I2C1_SDA_54") (pintype "input"))
    )
    (net (code "84") (name "unconnected-(IC1-P12_2_SIO-Pad67)") (class "Default")
      (node (ref "IC1") (pin "67") (pinfunction "P12_2_SIO_67") (pintype "input"))
    )
    (net (code "85") (name "unconnected-(IC1-P12_3_SIO-Pad68)") (class "Default")
      (node (ref "IC1") (pin "68") (pinfunction "P12_3_SIO_68") (pintype "input"))
    )
    (net (code "86") (name "unconnected-(IC1-P15_2_GPIO_KHZXTAL_XO-Pad55)") (class "Default")
      (node (ref "IC1") (pin "55") (pinfunction "P15_2_GPIO_KHZXTAL_XO_55") (pintype "input"))
    )
    (net (code "87") (name "unconnected-(IC1-SIO_P12_6-Pad29)") (class "Default")
      (node (ref "IC1") (pin "29") (pinfunction "SIO_P12_6_29") (pintype "input"))
    )
    (net (code "88") (name "unconnected-(IC1-SIO_P12_7-Pad30)") (class "Default")
      (node (ref "IC1") (pin "30") (pinfunction "SIO_P12_7_30") (pintype "input"))
    )
    (net (code "89") (name "unconnected-(J1-Pad4)") (class "Default")
      (node (ref "J1") (pin "4") (pinfunction "4_4") (pintype "input"))
    )
    (net (code "90") (name "unconnected-(J2-Pad8)") (class "Default")
      (node (ref "J2") (pin "8") (pinfunction "8_8") (pintype "input"))
    )
    (net (code "91") (name "unconnected-(J2-Pad9)") (class "Default")
      (node (ref "J2") (pin "9") (pinfunction "9_9") (pintype "input"))
    )
    (net (code "92") (name "unconnected-(SCSI50P-Pad25)") (class "Default")
      (node (ref "SCSI50P") (pin "25") (pinfunction "25_25") (pintype "passive"))
    )
    (net (code "93") (name "unconnected-(SD1-DAT1-Pad8)") (class "Default")
      (node (ref "SD1") (pin "8") (pinfunction "DAT1_8") (pintype "bidirectional"))
    )
    (net (code "94") (name "unconnected-(SD1-DAT2-Pad1)") (class "Default")
      (node (ref "SD1") (pin "1") (pinfunction "DAT2_1") (pintype "bidirectional"))
    )
  )
)
